# Thermokoppel.net
KiCad netlist of a schematic drawn in Altium Designer
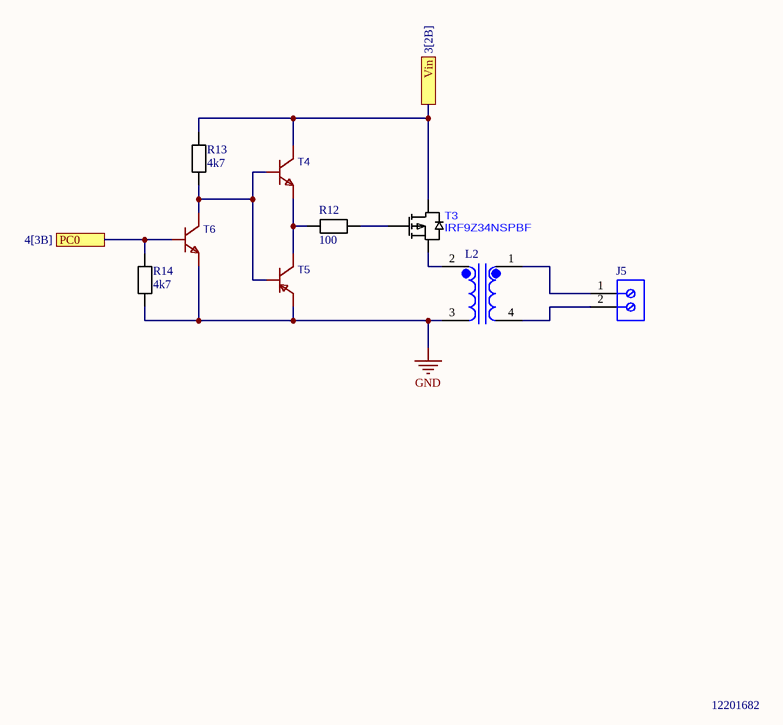
[diagram p0: Thermokoppel.SchDoc]

(export (version "E")
  (design (tool "Eeschema 10.0.6"))
  (components
    (comp (ref "J5")
      (value "691214110002")
      (footprint "2 Screw Terminal WE 691214110002")
      (description "Serie 2141 - 3.50 mm Horizontal Entry Modular with Rising Cage Clamp WR-TBL, 2 pin")
      (fields (field (name "MANUFACTURER") "Wurth Elektronik") (field (name "PUBLISHER") "WurthElektronik"))
      (libsource (lib "Soldering_Station_Library") (part "2 Screw Terminal WE 691214110002"))
    )
    (comp (ref "L2")
      (value "CM2545X171B-10")
      (footprint "CM2545X171B-10")
      (description "2 Line Common Mode Choke Through Hole 170 Ohms @ 100 MHz 10A DCR 10mOhm")
      (fields (field (name "MF") "Laird"))
      (libsource (lib "Soldering_Station_Library") (part "CM2545X171B-10"))
    )
    (comp (ref "R12")
      (value "100")
      (footprint "R0805")
      (fields (field (name "MANUFACTURER") "Vishay Dale") (field (name "PART NUMBER") "CRCW08050000Z0EA"))
      (libsource (lib "Soldering_Station_Library") (part "Resistor"))
    )
    (comp (ref "R13")
      (value "4k7")
      (footprint "R0805")
      (fields (field (name "MANUFACTURER") "Vishay Dale") (field (name "PART NUMBER") "CRCW08050000Z0EA"))
      (libsource (lib "Soldering_Station_Library") (part "Resistor"))
    )
    (comp (ref "R14")
      (value "4k7")
      (footprint "R0805")
      (fields (field (name "MANUFACTURER") "Vishay Dale") (field (name "PART NUMBER") "CRCW08050000Z0EA"))
      (libsource (lib "Soldering_Station_Library") (part "Resistor"))
    )
    (comp (ref "T3")
      (value "IRF9Z34NSPBF")
      (footprint "IRF9Z34NSPBF")
      (libsource (lib "Soldering_Station_Library") (part "IRF9Z34NSPBF"))
    )
    (comp (ref "T4")
      (value "BC847C_C3027113")
      (footprint "BC847_PNP")
      (fields
        (field (name "BOM_SUPPLIER PART") "C3027113")
        (field (name "BOM_MANUFACTURER PART") "BC847C")
        (field (name "CONTRIBUTOR") "lcsc")
      )
      (libsource (lib "Soldering_Station_Library") (part "BC847C_NPN"))
    )
    (comp (ref "T5")
      (value "BC857 3G")
      (footprint "BC847C_NPN")
      (fields (field (name "BOM_MANUFACTURER PART") "BC857") (field (name "BOM_SUPPLIER PART") "C2139"))
      (libsource (lib "Soldering_Station_Library") (part "BC847_PNP"))
    )
    (comp (ref "T6")
      (value "BC847C_C3027113")
      (footprint "BC847_PNP")
      (fields
        (field (name "BOM_SUPPLIER PART") "C3027113")
        (field (name "BOM_MANUFACTURER PART") "BC847C")
        (field (name "CONTRIBUTOR") "lcsc")
      )
      (libsource (lib "Soldering_Station_Library") (part "BC847C_NPN"))
    )
  )
  (nets
    (net (code "1") (name "/PC0") (class "Default")
      (node (ref "R14") (pin "2") (pinfunction "2_2") (pintype "passive"))
      (node (ref "T6") (pin "1") (pinfunction "B_1") (pintype "passive"))
    )
    (net (code "2") (name "/Vin") (class "Default")
      (node (ref "R13") (pin "2") (pinfunction "2_2") (pintype "passive"))
      (node (ref "T3") (pin "2") (pinfunction "D_2") (pintype "passive"))
      (node (ref "T4") (pin "3") (pinfunction "C_3") (pintype "passive"))
    )
    (net (code "3") (name "GND") (class "Default")
      (node (ref "L2") (pin "3") (pinfunction "3_3") (pintype "passive"))
      (node (ref "R14") (pin "1") (pinfunction "1_1") (pintype "passive"))
      (node (ref "T5") (pin "2") (pinfunction "2_2") (pintype "passive"))
      (node (ref "T6") (pin "2") (pinfunction "E_2") (pintype "passive"))
    )
    (net (code "4") (name "Net-(J5-Pad1)") (class "Default")
      (node (ref "J5") (pin "1") (pinfunction "1_1") (pintype "passive"))
      (node (ref "L2") (pin "1") (pinfunction "1_1") (pintype "passive"))
    )
    (net (code "5") (name "Net-(J5-Pad2)") (class "Default")
      (node (ref "J5") (pin "2") (pinfunction "2_2") (pintype "passive"))
      (node (ref "L2") (pin "4") (pinfunction "4_4") (pintype "passive"))
    )
    (net (code "6") (name "Net-(R12-Pad2)") (class "Default")
      (node (ref "R12") (pin "2") (pinfunction "2_2") (pintype "passive"))
      (node (ref "T3") (pin "4") (pinfunction "4_4") (pintype "passive"))
    )
    (net (code "7") (name "Net-(T3-S)") (class "Default")
      (node (ref "L2") (pin "2") (pinfunction "2_2") (pintype "passive"))
      (node (ref "T3") (pin "3") (pinfunction "S_3") (pintype "passive"))
    )
    (net (code "8") (name "Net-(T4-B)") (class "Default")
      (node (ref "R13") (pin "1") (pinfunction "1_1") (pintype "passive"))
      (node (ref "T4") (pin "1") (pinfunction "B_1") (pintype "passive"))
      (node (ref "T5") (pin "1") (pinfunction "1_1") (pintype "passive"))
      (node (ref "T6") (pin "3") (pinfunction "C_3") (pintype "passive"))
    )
    (net (code "9") (name "Net-(T4-E)") (class "Default")
      (node (ref "R12") (pin "1") (pinfunction "1_1") (pintype "passive"))
      (node (ref "T4") (pin "2") (pinfunction "E_2") (pintype "passive"))
      (node (ref "T5") (pin "3") (pinfunction "3_3") (pintype "passive"))
    )
  )
)
